# Atmel1.net
KiCad netlist of a schematic drawn in Altium Designer
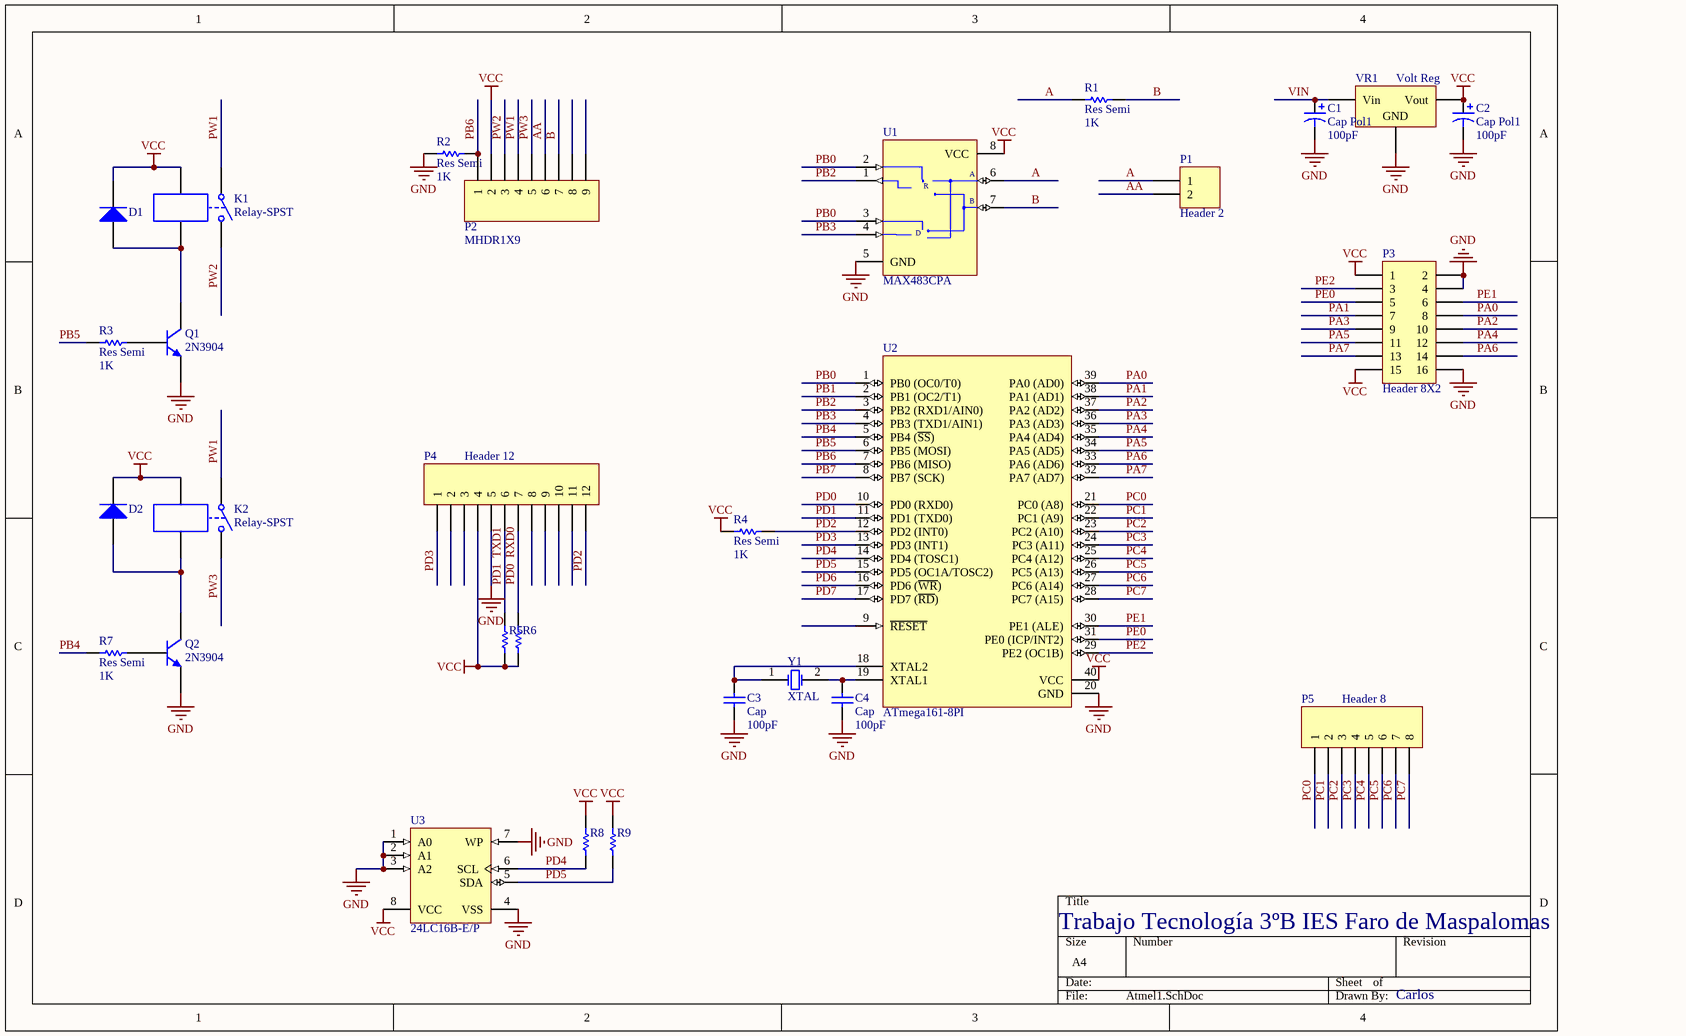
[diagram p0: Atmel1.SchDoc]

(export (version "E")
  (design (tool "Eeschema 10.0.6"))
  (components
    (comp (ref "C1")
      (value "Cap Pol1")
      (footprint "RB7.6-15")
      (description "Polarized Capacitor (Radial)")
      (fields (field (name "ALTIUM_VALUE") "100pF") (field (name "PUBLISHER") "Altium Limited"))
      (libsource (lib "Miscellaneous Devices") (part "Cap Pol1"))
    )
    (comp (ref "C2")
      (value "Cap Pol1")
      (footprint "RB7.6-15")
      (description "Polarized Capacitor (Radial)")
      (fields (field (name "ALTIUM_VALUE") "100pF") (field (name "PUBLISHER") "Altium Limited"))
      (libsource (lib "Miscellaneous Devices") (part "Cap Pol1"))
    )
    (comp (ref "C3")
      (value "Cap")
      (footprint "RAD-0.3")
      (description "Capacitor")
      (fields (field (name "ALTIUM_VALUE") "100pF") (field (name "PUBLISHER") "Altium Limited"))
      (libsource (lib "Miscellaneous Devices") (part "Cap"))
    )
    (comp (ref "C4")
      (value "Cap")
      (footprint "RAD-0.3")
      (description "Capacitor")
      (fields (field (name "ALTIUM_VALUE") "100pF") (field (name "PUBLISHER") "Altium Limited"))
      (libsource (lib "Miscellaneous Devices") (part "Cap"))
    )
    (comp (ref "D1")
      (value "Diode 1N4148")
      (footprint "DO-35")
      (description "High Conductance Fast Diode")
      (fields (field (name "PUBLISHER") "Altium Limited"))
      (libsource (lib "Miscellaneous Devices") (part "Diode 1N4148"))
    )
    (comp (ref "D2")
      (value "Diode 1N4148")
      (footprint "DO-35")
      (description "High Conductance Fast Diode")
      (fields (field (name "PUBLISHER") "Altium Limited"))
      (libsource (lib "Miscellaneous Devices") (part "Diode 1N4148"))
    )
    (comp (ref "K1")
      (value "Relay-SPST")
      (footprint "MODULE4")
      (description "Single-Pole Single-Throw Relay")
      (fields (field (name "PUBLISHER") "Altium Limited"))
      (libsource (lib "Miscellaneous Devices") (part "Relay-SPST"))
    )
    (comp (ref "K2")
      (value "Relay-SPST")
      (footprint "MODULE4")
      (description "Single-Pole Single-Throw Relay")
      (fields (field (name "PUBLISHER") "Altium Limited"))
      (libsource (lib "Miscellaneous Devices") (part "Relay-SPST"))
    )
    (comp (ref "P1")
      (value "Header 2")
      (footprint "HDR1X2")
      (description "Header, 2-Pin")
      (fields (field (name "PUBLISHER") "Altium Limited"))
      (libsource (lib "Miscellaneous Connectors") (part "Header 2"))
    )
    (comp (ref "P2")
      (value "MHDR1X9")
      (footprint "MHDR1X9")
      (description "Header, 9-Pin")
      (fields (field (name "PUBLISHER") "Altium Limited"))
      (libsource (lib "Miscellaneous Connectors") (part "MHDR1X9"))
    )
    (comp (ref "P3")
      (value "Header 8X2")
      (footprint "HDR2X8")
      (description "Header, 8-Pin, Dual row")
      (fields (field (name "PUBLISHER") "Altium Limited"))
      (libsource (lib "Miscellaneous Connectors") (part "Header 8X2"))
    )
    (comp (ref "P4")
      (value "Header 12")
      (footprint "HDR1X12")
      (description "Header, 12-Pin")
      (fields (field (name "PUBLISHER") "Altium Limited"))
      (libsource (lib "Miscellaneous Connectors") (part "Header 12"))
    )
    (comp (ref "P5")
      (value "Header 8")
      (footprint "HDR1X8")
      (description "Header, 8-Pin")
      (fields (field (name "PUBLISHER") "Altium Limited"))
      (libsource (lib "Miscellaneous Connectors") (part "Header 8"))
    )
    (comp (ref "Q1")
      (value "2N3904")
      (footprint "TO-92A")
      (description "NPN General Purpose Amplifier")
      (fields (field (name "PUBLISHER") "Altium Limited"))
      (libsource (lib "Miscellaneous Devices") (part "2N3904"))
    )
    (comp (ref "Q2")
      (value "2N3904")
      (footprint "TO-92A")
      (description "NPN General Purpose Amplifier")
      (fields (field (name "PUBLISHER") "Altium Limited"))
      (libsource (lib "Miscellaneous Devices") (part "2N3904"))
    )
    (comp (ref "R1")
      (value "Res Semi")
      (footprint "AXIAL-0.5")
      (description "Semiconductor Resistor")
      (fields (field (name "ALTIUM_VALUE") "1K") (field (name "PUBLISHER") "Altium Limited"))
      (libsource (lib "Miscellaneous Devices") (part "Res Semi"))
    )
    (comp (ref "R2")
      (value "Res Semi")
      (footprint "AXIAL-0.5")
      (description "Semiconductor Resistor")
      (fields (field (name "ALTIUM_VALUE") "1K") (field (name "PUBLISHER") "Altium Limited"))
      (libsource (lib "Miscellaneous Devices") (part "Res Semi"))
    )
    (comp (ref "R3")
      (value "Res Semi")
      (footprint "AXIAL-0.5")
      (description "Semiconductor Resistor")
      (fields (field (name "ALTIUM_VALUE") "1K") (field (name "PUBLISHER") "Altium Limited"))
      (libsource (lib "Miscellaneous Devices") (part "Res Semi"))
    )
    (comp (ref "R4")
      (value "Res Semi")
      (footprint "AXIAL-0.5")
      (description "Semiconductor Resistor")
      (fields (field (name "ALTIUM_VALUE") "1K") (field (name "PUBLISHER") "Altium Limited"))
      (libsource (lib "Miscellaneous Devices") (part "Res Semi"))
    )
    (comp (ref "R5")
      (value "Res Semi")
      (footprint "AXIAL-0.5")
      (description "Semiconductor Resistor")
      (fields (field (name "PUBLISHER") "Altium Limited"))
      (libsource (lib "Miscellaneous Devices") (part "Res Semi"))
    )
    (comp (ref "R6")
      (value "Res Semi")
      (footprint "AXIAL-0.5")
      (description "Semiconductor Resistor")
      (fields (field (name "PUBLISHER") "Altium Limited"))
      (libsource (lib "Miscellaneous Devices") (part "Res Semi"))
    )
    (comp (ref "R7")
      (value "Res Semi")
      (footprint "AXIAL-0.5")
      (description "Semiconductor Resistor")
      (fields (field (name "ALTIUM_VALUE") "1K") (field (name "PUBLISHER") "Altium Limited"))
      (libsource (lib "Miscellaneous Devices") (part "Res Semi"))
    )
    (comp (ref "R8")
      (value "Res Semi")
      (footprint "AXIAL-0.5")
      (description "Semiconductor Resistor")
      (fields (field (name "PUBLISHER") "Altium Limited"))
      (libsource (lib "Miscellaneous Devices") (part "Res Semi"))
    )
    (comp (ref "R9")
      (value "Res Semi")
      (footprint "AXIAL-0.5")
      (description "Semiconductor Resistor")
      (fields (field (name "PUBLISHER") "Altium Limited"))
      (libsource (lib "Miscellaneous Devices") (part "Res Semi"))
    )
    (comp (ref "U1")
      (value "MAX483CPA")
      (footprint "PA8")
      (description "Low-Power, Slew-Rate-Limited RS-485/RS-422 Transceiver")
      (fields (field (name "PUBLISHER") "Altium Limited"))
      (libsource (lib "Maxim Communication Transceiver") (part "MAX483CPA"))
    )
    (comp (ref "U2")
      (value "ATmega161-8PI")
      (footprint "40P6")
      (description "8-Bit AVR Microcontroller with 16K Bytes of In-System Programmable Flash Memory")
      (fields (field (name "PUBLISHER") "Altium Limited"))
      (libsource (lib "Atmel Microcontroller 8-Bit AVR") (part "ATmega161-8PI"))
    )
    (comp (ref "U3")
      (value "24LC16B-E/P")
      (footprint "PDIP300-P8")
      (description "16Kbit, 400kHz, 2.5V, I2C Serial EEPROM, 8-Pin PDIP, Extended Temperature")
      (fields (field (name "PUBLISHER") "Altium Limited"))
      (libsource (lib "Microchip Memory I2C Serial EEPROM") (part "24LC16B-E/P"))
    )
    (comp (ref "VR1")
      (value "Volt Reg")
      (footprint "D2PAK_N")
      (description "Voltage Regulator")
      (fields (field (name "PUBLISHER") "Altium Limited"))
      (libsource (lib "Miscellaneous Devices") (part "Volt Reg"))
    )
    (comp (ref "Y1")
      (value "XTAL")
      (footprint "R38")
      (description "Crystal Oscillator")
      (fields (field (name "PUBLISHER") "Altium Limited"))
      (libsource (lib "Miscellaneous Devices") (part "XTAL"))
    )
  )
  (nets
    (net (code "1") (name "/A") (class "Default")
      (node (ref "P1") (pin "1") (pinfunction "1_1") (pintype "passive"))
      (node (ref "R1") (pin "1") (pinfunction "1_1") (pintype "passive"))
      (node (ref "U1") (pin "6") (pinfunction "A_6") (pintype "bidirectional"))
    )
    (net (code "2") (name "/AA") (class "Default")
      (node (ref "P1") (pin "2") (pinfunction "2_2") (pintype "passive"))
      (node (ref "P2") (pin "6") (pinfunction "6_6") (pintype "passive"))
    )
    (net (code "3") (name "/B") (class "Default")
      (node (ref "P2") (pin "7") (pinfunction "7_7") (pintype "passive"))
      (node (ref "R1") (pin "2") (pinfunction "2_2") (pintype "passive"))
      (node (ref "U1") (pin "7") (pinfunction "B_7") (pintype "bidirectional"))
    )
    (net (code "4") (name "/PA0") (class "Default")
      (node (ref "P3") (pin "8") (pinfunction "8_8") (pintype "passive"))
      (node (ref "U2") (pin "39") (pinfunction "PA0_(AD0)_39") (pintype "bidirectional"))
    )
    (net (code "5") (name "/PA1") (class "Default")
      (node (ref "P3") (pin "7") (pinfunction "7_7") (pintype "passive"))
      (node (ref "U2") (pin "38") (pinfunction "PA1_(AD1)_38") (pintype "bidirectional"))
    )
    (net (code "6") (name "/PA2") (class "Default")
      (node (ref "P3") (pin "10") (pinfunction "10_10") (pintype "passive"))
      (node (ref "U2") (pin "37") (pinfunction "PA2_(AD2)_37") (pintype "bidirectional"))
    )
    (net (code "7") (name "/PA3") (class "Default")
      (node (ref "P3") (pin "9") (pinfunction "9_9") (pintype "passive"))
      (node (ref "U2") (pin "36") (pinfunction "PA3_(AD3)_36") (pintype "bidirectional"))
    )
    (net (code "8") (name "/PA4") (class "Default")
      (node (ref "P3") (pin "12") (pinfunction "12_12") (pintype "passive"))
      (node (ref "U2") (pin "35") (pinfunction "PA4_(AD4)_35") (pintype "bidirectional"))
    )
    (net (code "9") (name "/PA5") (class "Default")
      (node (ref "P3") (pin "11") (pinfunction "11_11") (pintype "passive"))
      (node (ref "U2") (pin "34") (pinfunction "PA5_(AD5)_34") (pintype "bidirectional"))
    )
    (net (code "10") (name "/PA6") (class "Default")
      (node (ref "P3") (pin "14") (pinfunction "14_14") (pintype "passive"))
      (node (ref "U2") (pin "33") (pinfunction "PA6_(AD6)_33") (pintype "bidirectional"))
    )
    (net (code "11") (name "/PA7") (class "Default")
      (node (ref "P3") (pin "13") (pinfunction "13_13") (pintype "passive"))
      (node (ref "U2") (pin "32") (pinfunction "PA7_(AD7)_32") (pintype "bidirectional"))
    )
    (net (code "12") (name "/PB0") (class "Default")
      (node (ref "U1") (pin "2") (pinfunction "~{RE}_2") (pintype "input"))
      (node (ref "U1") (pin "3") (pinfunction "DE_3") (pintype "input"))
      (node (ref "U2") (pin "1") (pinfunction "PB0_(OC0/T0)_1") (pintype "bidirectional"))
    )
    (net (code "13") (name "/PB1") (class "Default")
      (node (ref "U2") (pin "2") (pinfunction "PB1_(OC2/T1)_2") (pintype "bidirectional"))
    )
    (net (code "14") (name "/PB2") (class "Default")
      (node (ref "U1") (pin "1") (pinfunction "RO_1") (pintype "output"))
      (node (ref "U2") (pin "3") (pinfunction "PB2_(RXD1/AIN0)_3") (pintype "bidirectional"))
    )
    (net (code "15") (name "/PB3") (class "Default")
      (node (ref "U1") (pin "4") (pinfunction "DI_4") (pintype "input"))
      (node (ref "U2") (pin "4") (pinfunction "PB3_(TXD1/AIN1)_4") (pintype "bidirectional"))
    )
    (net (code "16") (name "/PB4") (class "Default")
      (node (ref "R7") (pin "1") (pinfunction "1_1") (pintype "passive"))
      (node (ref "U2") (pin "5") (pinfunction "PB4_(~{SS})_5") (pintype "bidirectional"))
    )
    (net (code "17") (name "/PB5") (class "Default")
      (node (ref "R3") (pin "1") (pinfunction "1_1") (pintype "passive"))
      (node (ref "U2") (pin "6") (pinfunction "PB5_(MOSI)_6") (pintype "bidirectional"))
    )
    (net (code "18") (name "/PB6") (class "Default")
      (node (ref "P2") (pin "1") (pinfunction "1_1") (pintype "passive"))
      (node (ref "R2") (pin "2") (pinfunction "2_2") (pintype "passive"))
      (node (ref "U2") (pin "7") (pinfunction "PB6_(MISO)_7") (pintype "bidirectional"))
    )
    (net (code "19") (name "/PB7") (class "Default")
      (node (ref "U2") (pin "8") (pinfunction "PB7_(SCK)_8") (pintype "bidirectional"))
    )
    (net (code "20") (name "/PC0") (class "Default")
      (node (ref "P5") (pin "1") (pinfunction "1_1") (pintype "passive"))
      (node (ref "U2") (pin "21") (pinfunction "PC0_(A8)_21") (pintype "bidirectional"))
    )
    (net (code "21") (name "/PC1") (class "Default")
      (node (ref "P5") (pin "2") (pinfunction "2_2") (pintype "passive"))
      (node (ref "U2") (pin "22") (pinfunction "PC1_(A9)_22") (pintype "bidirectional"))
    )
    (net (code "22") (name "/PC2") (class "Default")
      (node (ref "P5") (pin "3") (pinfunction "3_3") (pintype "passive"))
      (node (ref "U2") (pin "23") (pinfunction "PC2_(A10)_23") (pintype "bidirectional"))
    )
    (net (code "23") (name "/PC3") (class "Default")
      (node (ref "P5") (pin "4") (pinfunction "4_4") (pintype "passive"))
      (node (ref "U2") (pin "24") (pinfunction "PC3_(A11)_24") (pintype "bidirectional"))
    )
    (net (code "24") (name "/PC4") (class "Default")
      (node (ref "P5") (pin "5") (pinfunction "5_5") (pintype "passive"))
      (node (ref "U2") (pin "25") (pinfunction "PC4_(A12)_25") (pintype "bidirectional"))
    )
    (net (code "25") (name "/PC5") (class "Default")
      (node (ref "P5") (pin "6") (pinfunction "6_6") (pintype "passive"))
      (node (ref "U2") (pin "26") (pinfunction "PC5_(A13)_26") (pintype "bidirectional"))
    )
    (net (code "26") (name "/PC6") (class "Default")
      (node (ref "P5") (pin "7") (pinfunction "7_7") (pintype "passive"))
      (node (ref "U2") (pin "27") (pinfunction "PC6_(A14)_27") (pintype "bidirectional"))
    )
    (net (code "27") (name "/PC7") (class "Default")
      (node (ref "P5") (pin "8") (pinfunction "8_8") (pintype "passive"))
      (node (ref "U2") (pin "28") (pinfunction "PC7_(A15)_28") (pintype "bidirectional"))
    )
    (net (code "28") (name "/PD0") (class "Default")
      (node (ref "P4") (pin "7") (pinfunction "7_7") (pintype "passive"))
      (node (ref "R6") (pin "2") (pinfunction "2_2") (pintype "passive"))
      (node (ref "U2") (pin "10") (pinfunction "PD0_(RXD0)_10") (pintype "bidirectional"))
    )
    (net (code "29") (name "/PD1") (class "Default")
      (node (ref "P4") (pin "6") (pinfunction "6_6") (pintype "passive"))
      (node (ref "R5") (pin "2") (pinfunction "2_2") (pintype "passive"))
      (node (ref "U2") (pin "11") (pinfunction "PD1_(TXD0)_11") (pintype "bidirectional"))
    )
    (net (code "30") (name "/PD2") (class "Default")
      (node (ref "P4") (pin "12") (pinfunction "12_12") (pintype "passive"))
      (node (ref "R4") (pin "2") (pinfunction "2_2") (pintype "passive"))
      (node (ref "U2") (pin "12") (pinfunction "PD2_(INT0)_12") (pintype "bidirectional"))
    )
    (net (code "31") (name "/PD3") (class "Default")
      (node (ref "P4") (pin "1") (pinfunction "1_1") (pintype "passive"))
      (node (ref "U2") (pin "13") (pinfunction "PD3_(INT1)_13") (pintype "bidirectional"))
    )
    (net (code "32") (name "/PD4") (class "Default")
      (node (ref "R8") (pin "1") (pinfunction "1_1") (pintype "passive"))
      (node (ref "U2") (pin "14") (pinfunction "PD4_(TOSC1)_14") (pintype "bidirectional"))
      (node (ref "U3") (pin "6") (pinfunction "SCL_6") (pintype "input"))
    )
    (net (code "33") (name "/PD5") (class "Default")
      (node (ref "R9") (pin "1") (pinfunction "1_1") (pintype "passive"))
      (node (ref "U2") (pin "15") (pinfunction "PD5_(OC1A/TOSC2)_15") (pintype "bidirectional"))
      (node (ref "U3") (pin "5") (pinfunction "SDA_5") (pintype "bidirectional"))
    )
    (net (code "34") (name "/PD6") (class "Default")
      (node (ref "U2") (pin "16") (pinfunction "PD6_(~{WR})_16") (pintype "bidirectional"))
    )
    (net (code "35") (name "/PD7") (class "Default")
      (node (ref "U2") (pin "17") (pinfunction "PD7_(~{RD})_17") (pintype "bidirectional"))
    )
    (net (code "36") (name "/PE0") (class "Default")
      (node (ref "P3") (pin "5") (pinfunction "5_5") (pintype "passive"))
      (node (ref "U2") (pin "31") (pinfunction "PE0_(ICP/INT2)_31") (pintype "bidirectional"))
    )
    (net (code "37") (name "/PE1") (class "Default")
      (node (ref "P3") (pin "6") (pinfunction "6_6") (pintype "passive"))
      (node (ref "U2") (pin "30") (pinfunction "PE1_(ALE)_30") (pintype "bidirectional"))
    )
    (net (code "38") (name "/PE2") (class "Default")
      (node (ref "P3") (pin "3") (pinfunction "3_3") (pintype "passive"))
      (node (ref "U2") (pin "29") (pinfunction "PE2_(OC1B)_29") (pintype "bidirectional"))
    )
    (net (code "39") (name "/PW1") (class "Default")
      (node (ref "K1") (pin "1") (pinfunction "1_1") (pintype "passive"))
      (node (ref "K2") (pin "1") (pinfunction "1_1") (pintype "passive"))
      (node (ref "P2") (pin "4") (pinfunction "4_4") (pintype "passive"))
    )
    (net (code "40") (name "/PW2") (class "Default")
      (node (ref "K1") (pin "2") (pinfunction "2_2") (pintype "passive"))
      (node (ref "P2") (pin "3") (pinfunction "3_3") (pintype "passive"))
    )
    (net (code "41") (name "/PW3") (class "Default")
      (node (ref "K2") (pin "2") (pinfunction "2_2") (pintype "passive"))
      (node (ref "P2") (pin "5") (pinfunction "5_5") (pintype "passive"))
    )
    (net (code "42") (name "/VIN") (class "Default")
      (node (ref "C1") (pin "1") (pinfunction "1_1") (pintype "passive"))
      (node (ref "VR1") (pin "1") (pinfunction "Vin_1") (pintype "passive"))
    )
    (net (code "43") (name "GND") (class "Default")
      (node (ref "C1") (pin "2") (pinfunction "2_2") (pintype "passive"))
      (node (ref "C2") (pin "2") (pinfunction "2_2") (pintype "passive"))
      (node (ref "C3") (pin "1") (pinfunction "1_1") (pintype "passive"))
      (node (ref "C4") (pin "1") (pinfunction "1_1") (pintype "passive"))
      (node (ref "P3") (pin "16") (pinfunction "16_16") (pintype "passive"))
      (node (ref "P3") (pin "2") (pinfunction "2_2") (pintype "passive"))
      (node (ref "P3") (pin "4") (pinfunction "4_4") (pintype "passive"))
      (node (ref "P4") (pin "5") (pinfunction "5_5") (pintype "passive"))
      (node (ref "Q1") (pin "1") (pinfunction "E_1") (pintype "passive"))
      (node (ref "Q2") (pin "1") (pinfunction "E_1") (pintype "passive"))
      (node (ref "R2") (pin "1") (pinfunction "1_1") (pintype "passive"))
      (node (ref "U1") (pin "5") (pinfunction "GND_5") (pintype "power_in"))
      (node (ref "U2") (pin "20") (pinfunction "GND_20") (pintype "power_in"))
      (node (ref "U3") (pin "1") (pinfunction "A0_1") (pintype "input"))
      (node (ref "U3") (pin "2") (pinfunction "A1_2") (pintype "input"))
      (node (ref "U3") (pin "3") (pinfunction "A2_3") (pintype "input"))
      (node (ref "U3") (pin "4") (pinfunction "VSS_4") (pintype "power_in"))
      (node (ref "U3") (pin "7") (pinfunction "WP_7") (pintype "input"))
      (node (ref "VR1") (pin "2") (pinfunction "GND_2") (pintype "passive"))
    )
    (net (code "44") (name "Net-(D1-A)") (class "Default")
      (node (ref "D1") (pin "1") (pinfunction "A_1") (pintype "passive"))
      (node (ref "K1") (pin "4") (pinfunction "4_4") (pintype "passive"))
      (node (ref "Q1") (pin "3") (pinfunction "C_3") (pintype "passive"))
    )
    (net (code "45") (name "Net-(D2-A)") (class "Default")
      (node (ref "D2") (pin "1") (pinfunction "A_1") (pintype "passive"))
      (node (ref "K2") (pin "4") (pinfunction "4_4") (pintype "passive"))
      (node (ref "Q2") (pin "3") (pinfunction "C_3") (pintype "passive"))
    )
    (net (code "46") (name "Net-(Q1-B)") (class "Default")
      (node (ref "Q1") (pin "2") (pinfunction "B_2") (pintype "passive"))
      (node (ref "R3") (pin "2") (pinfunction "2_2") (pintype "passive"))
    )
    (net (code "47") (name "Net-(Q2-B)") (class "Default")
      (node (ref "Q2") (pin "2") (pinfunction "B_2") (pintype "passive"))
      (node (ref "R7") (pin "2") (pinfunction "2_2") (pintype "passive"))
    )
    (net (code "48") (name "Net-(U2-XTAL1)") (class "Default")
      (node (ref "C4") (pin "2") (pinfunction "2_2") (pintype "passive"))
      (node (ref "U2") (pin "19") (pinfunction "XTAL1_19") (pintype "passive"))
      (node (ref "Y1") (pin "2") (pinfunction "OSC2_2") (pintype "passive"))
    )
    (net (code "49") (name "Net-(U2-XTAL2)") (class "Default")
      (node (ref "C3") (pin "2") (pinfunction "2_2") (pintype "passive"))
      (node (ref "U2") (pin "18") (pinfunction "XTAL2_18") (pintype "passive"))
      (node (ref "Y1") (pin "1") (pinfunction "OSC1_1") (pintype "passive"))
    )
    (net (code "50") (name "VCC") (class "Default")
      (node (ref "C2") (pin "1") (pinfunction "1_1") (pintype "passive"))
      (node (ref "D1") (pin "2") (pinfunction "K_2") (pintype "passive"))
      (node (ref "D2") (pin "2") (pinfunction "K_2") (pintype "passive"))
      (node (ref "K1") (pin "3") (pinfunction "3_3") (pintype "passive"))
      (node (ref "K2") (pin "3") (pinfunction "3_3") (pintype "passive"))
      (node (ref "P2") (pin "2") (pinfunction "2_2") (pintype "passive"))
      (node (ref "P3") (pin "1") (pinfunction "1_1") (pintype "passive"))
      (node (ref "P3") (pin "15") (pinfunction "15_15") (pintype "passive"))
      (node (ref "P4") (pin "4") (pinfunction "4_4") (pintype "passive"))
      (node (ref "R4") (pin "1") (pinfunction "1_1") (pintype "passive"))
      (node (ref "R5") (pin "1") (pinfunction "1_1") (pintype "passive"))
      (node (ref "R6") (pin "1") (pinfunction "1_1") (pintype "passive"))
      (node (ref "R8") (pin "2") (pinfunction "2_2") (pintype "passive"))
      (node (ref "R9") (pin "2") (pinfunction "2_2") (pintype "passive"))
      (node (ref "U1") (pin "8") (pinfunction "VCC_8") (pintype "power_in"))
      (node (ref "U2") (pin "40") (pinfunction "VCC_40") (pintype "power_in"))
      (node (ref "U3") (pin "8") (pinfunction "VCC_8") (pintype "power_in"))
      (node (ref "VR1") (pin "3") (pinfunction "Vout_3") (pintype "passive"))
    )
    (net (code "51") (name "unconnected-(P2-Pad8)") (class "Default")
      (node (ref "P2") (pin "8") (pinfunction "8_8") (pintype "passive"))
    )
    (net (code "52") (name "unconnected-(P2-Pad9)") (class "Default")
      (node (ref "P2") (pin "9") (pinfunction "9_9") (pintype "passive"))
    )
    (net (code "53") (name "unconnected-(P4-Pad2)") (class "Default")
      (node (ref "P4") (pin "2") (pinfunction "2_2") (pintype "passive"))
    )
    (net (code "54") (name "unconnected-(P4-Pad3)") (class "Default")
      (node (ref "P4") (pin "3") (pinfunction "3_3") (pintype "passive"))
    )
    (net (code "55") (name "unconnected-(P4-Pad8)") (class "Default")
      (node (ref "P4") (pin "8") (pinfunction "8_8") (pintype "passive"))
    )
    (net (code "56") (name "unconnected-(P4-Pad9)") (class "Default")
      (node (ref "P4") (pin "9") (pinfunction "9_9") (pintype "passive"))
    )
    (net (code "57") (name "unconnected-(P4-Pad10)") (class "Default")
      (node (ref "P4") (pin "10") (pinfunction "10_10") (pintype "passive"))
    )
    (net (code "58") (name "unconnected-(P4-Pad11)") (class "Default")
      (node (ref "P4") (pin "11") (pinfunction "11_11") (pintype "passive"))
    )
    (net (code "59") (name "unconnected-(U2-~{RESET}-Pad9)") (class "Default")
      (node (ref "U2") (pin "9") (pinfunction "~{RESET}_9") (pintype "input"))
    )
  )
)
